# CAN.net
KiCad netlist of a schematic drawn in Altium Designer
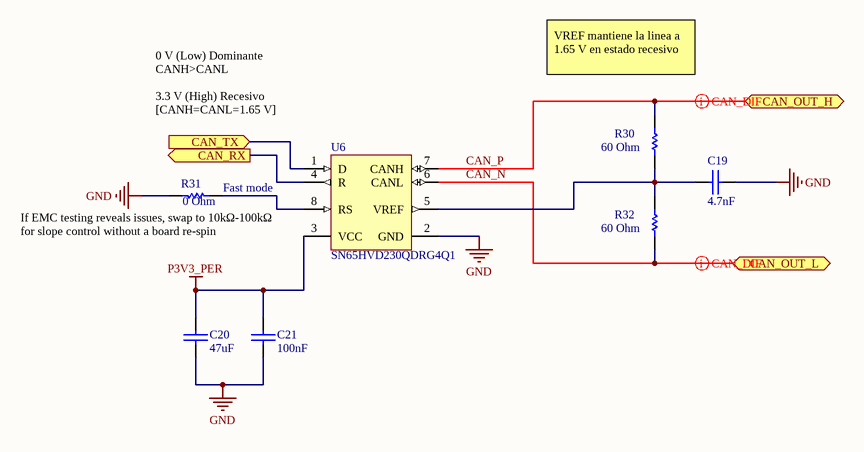
[diagram p0: CAN.SchDoc]

(export (version "E")
  (design (tool "Eeschema 10.0.6"))
  (components
    (comp (ref "C19")
      (value "4.7nF")
      (footprint "0603C")
      (description "Capacitor")
      (libsource (lib "MB1137") (part "CAP"))
    )
    (comp (ref "C20")
      (value "47uF")
      (footprint "0603C")
      (description "Capacitor")
      (libsource (lib "MB1137") (part "CAP"))
    )
    (comp (ref "C21")
      (value "100nF")
      (footprint "0603C")
      (description "Capacitor")
      (libsource (lib "MB1137") (part "CAP"))
    )
    (comp (ref "R30")
      (value "60 Ohm")
      (footprint "0603R")
      (description "Resistor")
      (fields (field (name "PUBLISHER") "Altium Limited"))
      (libsource (lib "MB1137") (part "Res1"))
    )
    (comp (ref "R31")
      (value "0 Ohm")
      (footprint "0603R")
      (description "Resistor")
      (fields (field (name "PUBLISHER") "Altium Limited"))
      (libsource (lib "Miscellaneous Devices") (part "Res1"))
    )
    (comp (ref "R32")
      (value "60 Ohm")
      (footprint "0603R")
      (description "Resistor")
      (fields (field (name "PUBLISHER") "Altium Limited"))
      (libsource (lib "MB1137") (part "Res1"))
    )
    (comp (ref "U6")
      (value "SN65HVD230QDRG4Q1")
      (footprint "D0008A_M")
      (fields (field (name "MANUFACTURER") "Texas Instruments"))
      (libsource (lib "Altium Content Vault") (part "TI-SN65HVD230Q-Q1-SOIC_D-8"))
    )
  )
  (nets
    (net (code "1") (name "/CAN_N") (class "Default")
      (node (ref "R32") (pin "1") (pinfunction "1_1") (pintype "passive"))
      (node (ref "U6") (pin "6") (pinfunction "CANL_6") (pintype "bidirectional"))
    )
    (net (code "2") (name "/CAN_P") (class "Default")
      (node (ref "R30") (pin "2") (pinfunction "2_2") (pintype "passive"))
      (node (ref "U6") (pin "7") (pinfunction "CANH_7") (pintype "bidirectional"))
    )
    (net (code "3") (name "/CAN_RX") (class "Default")
      (node (ref "U6") (pin "4") (pinfunction "R_4") (pintype "output"))
    )
    (net (code "4") (name "/CAN_TX") (class "Default")
      (node (ref "U6") (pin "1") (pinfunction "D_1") (pintype "input"))
    )
    (net (code "5") (name "GND") (class "Default")
      (node (ref "C19") (pin "2") (pinfunction "2_2") (pintype "passive"))
      (node (ref "C20") (pin "1") (pinfunction "1_1") (pintype "passive"))
      (node (ref "C21") (pin "1") (pinfunction "1_1") (pintype "passive"))
      (node (ref "R31") (pin "2") (pinfunction "2_2") (pintype "passive"))
      (node (ref "U6") (pin "2") (pinfunction "GND_2") (pintype "power_in"))
    )
    (net (code "6") (name "Net-(U6-RS)") (class "Default")
      (node (ref "R31") (pin "1") (pinfunction "1_1") (pintype "passive"))
      (node (ref "U6") (pin "8") (pinfunction "RS_8") (pintype "input"))
    )
    (net (code "7") (name "Net-(U6-VREF)") (class "Default")
      (node (ref "C19") (pin "1") (pinfunction "1_1") (pintype "passive"))
      (node (ref "R30") (pin "1") (pinfunction "1_1") (pintype "passive"))
      (node (ref "R32") (pin "2") (pinfunction "2_2") (pintype "passive"))
      (node (ref "U6") (pin "5") (pinfunction "VREF_5") (pintype "output"))
    )
    (net (code "8") (name "P3V3_PER") (class "Default")
      (node (ref "C20") (pin "2") (pinfunction "2_2") (pintype "passive"))
      (node (ref "C21") (pin "2") (pinfunction "2_2") (pintype "passive"))
      (node (ref "U6") (pin "3") (pinfunction "VCC_3") (pintype "power_in"))
    )
  )
)
